# Week09_InputDevice_MicBoard_ADLL_FabAcad.net
KiCad netlist of a schematic drawn in EAGLE
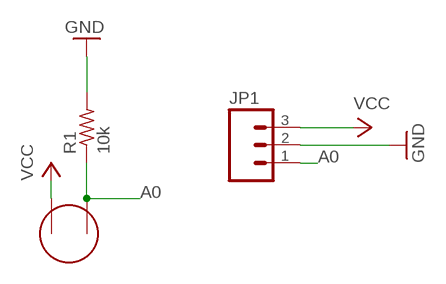
[diagram p0: schematic, sheet 1]

(export (version "E")
  (design (tool "Eeschema 10.0.6"))
  (components
    (comp (ref "JP1")
      (value "M03PTH")
      (footprint "eagle-import:1X03")
      (libsource (lib "eagle-import") (part "M03PTH"))
    )
    (comp (ref "R1")
      (value "10k")
      (footprint "eagle-import:1206")
      (libsource (lib "eagle-import") (part "RESISTOR1206"))
    )
    (comp (ref "U$2")
      (value "ELECTRET")
      (footprint "eagle-import:ELECTRET_2742PBJ-A")
      (libsource (lib "eagle-import") (part "ELECTRET"))
    )
  )
  (nets
    (net (code "1") (name "/A0") (class "Default")
      (node (ref "JP1") (pin "1") (pinfunction "1_1") (pintype "passive"))
      (node (ref "R1") (pin "1") (pinfunction "1_1") (pintype "passive"))
      (node (ref "U$2") (pin "P$1") (pinfunction "P$1_P$1") (pintype "bidirectional"))
    )
    (net (code "2") (name "GND") (class "Default")
      (node (ref "JP1") (pin "2") (pinfunction "2_2") (pintype "passive"))
      (node (ref "R1") (pin "2") (pinfunction "2_2") (pintype "passive"))
    )
    (net (code "3") (name "VCC") (class "Default")
      (node (ref "JP1") (pin "3") (pinfunction "3_3") (pintype "passive"))
      (node (ref "U$2") (pin "P$2") (pinfunction "P$2_P$2") (pintype "bidirectional"))
    )
  )
)
